# schematics_easyeda.net
KiCad netlist of a schematic drawn in EasyEDA
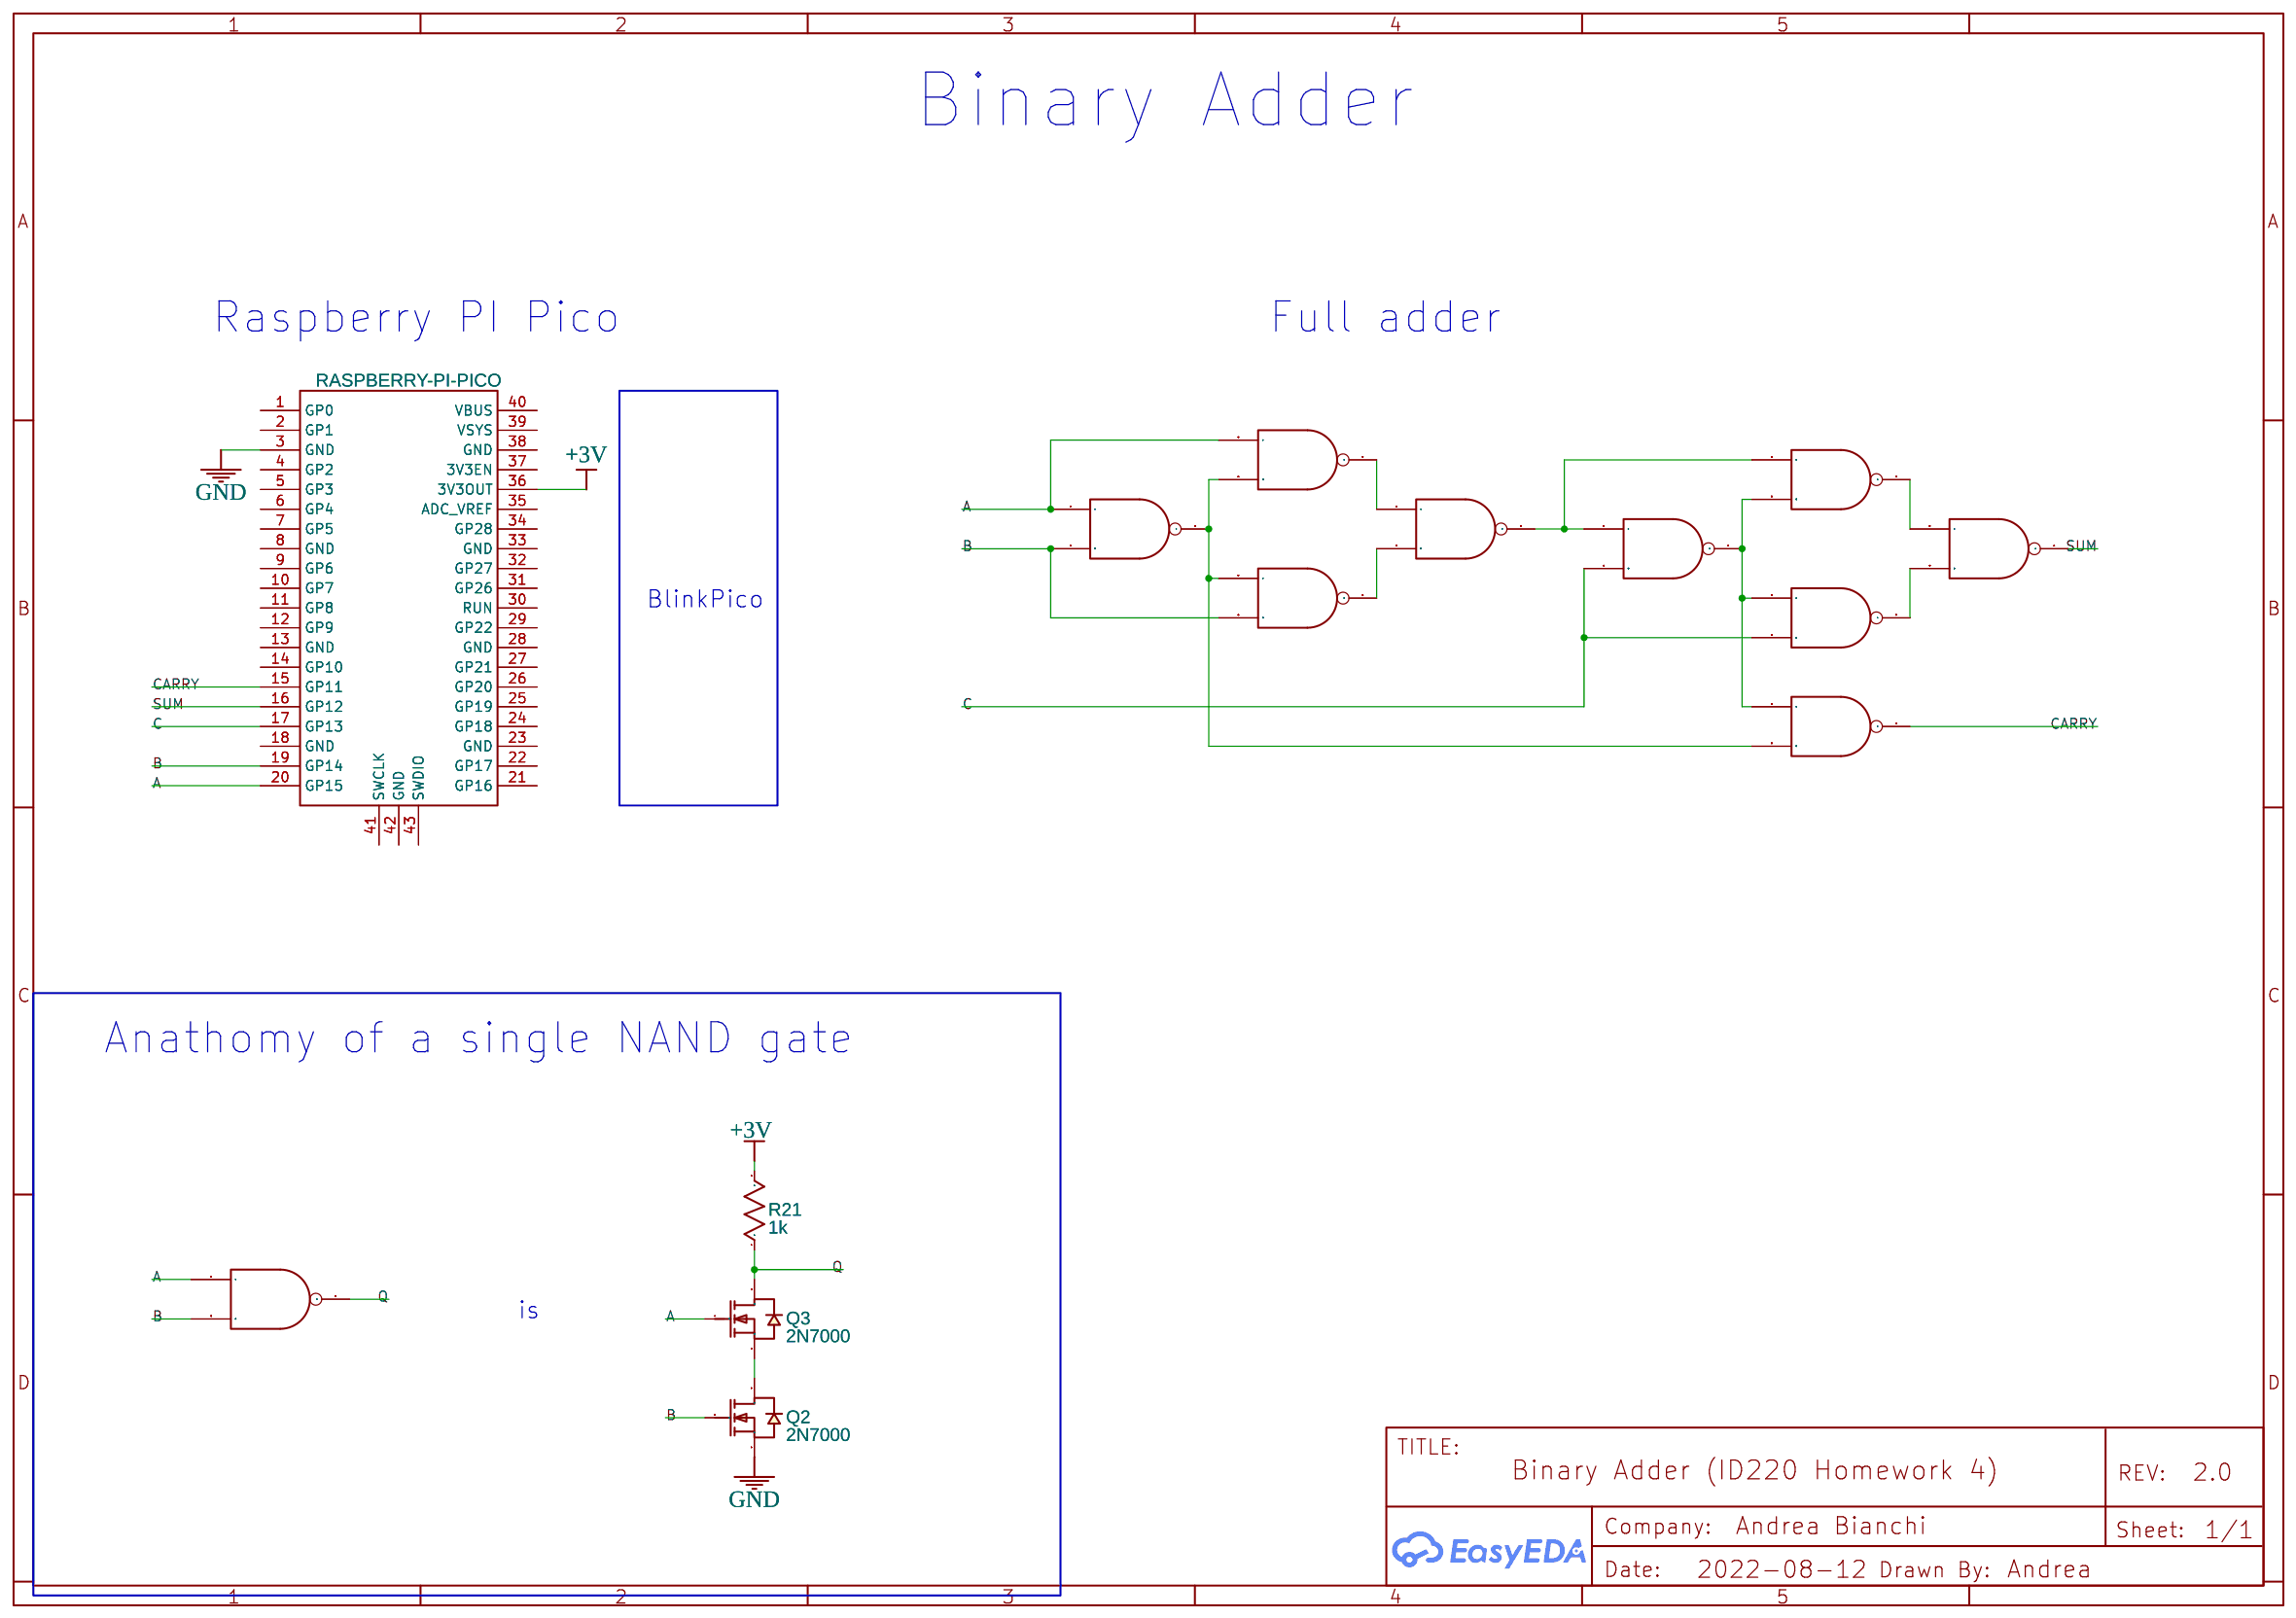
[diagram p0: schematic sheet]

(export (version "E")
  (design (tool "Eeschema 10.0.6"))
  (components
    (comp (ref "NAND1")
      (value "NO")
      (fields (field (name "BOM_Manufacturer Part") "?"))
      (libsource (lib "") (part "Unknown_565_-545"))
    )
    (comp (ref "NAND2")
      (value "NO")
      (fields (field (name "BOM_Manufacturer Part") "?"))
      (libsource (lib "") (part "Unknown_650_-580"))
    )
    (comp (ref "NAND3")
      (value "NO")
      (fields (field (name "BOM_Manufacturer Part") "?"))
      (libsource (lib "") (part "Unknown_650_-510"))
    )
    (comp (ref "NAND4")
      (value "NO")
      (fields (field (name "BOM_Manufacturer Part") "?"))
      (libsource (lib "") (part "Unknown_730_-545"))
    )
    (comp (ref "NAND5")
      (value "NO")
      (fields (field (name "BOM_Manufacturer Part") "?"))
      (libsource (lib "") (part "Unknown_1000_-535"))
    )
    (comp (ref "NAND6")
      (value "NO")
      (fields (field (name "BOM_Manufacturer Part") "?"))
      (libsource (lib "") (part "Unknown_920_-500"))
    )
    (comp (ref "NAND7")
      (value "NO")
      (fields (field (name "BOM_Manufacturer Part") "?"))
      (libsource (lib "") (part "Unknown_920_-570"))
    )
    (comp (ref "NAND8")
      (value "NO")
      (fields (field (name "BOM_Manufacturer Part") "?"))
      (libsource (lib "") (part "Unknown_835_-535"))
    )
    (comp (ref "NAND9")
      (value "NO")
      (fields (field (name "BOM_Manufacturer Part") "?"))
      (libsource (lib "") (part "Unknown_920_-445"))
    )
    (comp (ref "NAND10")
      (value "NO")
      (fields (field (name "BOM_Manufacturer Part") "?"))
      (libsource (lib "") (part "Unknown_130_-155"))
    )
    (comp (ref "Q2")
      (value "2N7000")
      (fields (field (name "BOM_Manufacturer Part") "2N7002,215") (field (name "BOM_Supplier Part") "C65189"))
      (libsource (lib "") (part "2N7002"))
    )
    (comp (ref "Q3")
      (value "2N7000")
      (fields (field (name "BOM_Manufacturer Part") "2N7002,215") (field (name "BOM_Supplier Part") "C65189"))
      (libsource (lib "") (part "2N7002"))
    )
    (comp (ref "R21") (value "1k") (libsource (lib "") (part "R_0603_US")))
    (comp (ref "U4") (value "RASPBERRY-PI-PICO") (libsource (lib "") (part "RASPBERRY-PI-PICO")))
  )
  (nets
    (net (code "1") (name "+3V") (class "Default")
      (node (ref "R21") (pin "2") (pinfunction "2_2") (pintype "unspecified"))
      (node (ref "U4") (pin "36") (pinfunction "3V3OUT_36") (pintype "unspecified"))
    )
    (net (code "2") (name "/A") (class "Default")
      (node (ref "NAND1") (pin "12") (pinfunction "A_12") (pintype "unspecified"))
      (node (ref "NAND10") (pin "12") (pinfunction "A_12") (pintype "unspecified"))
      (node (ref "NAND2") (pin "12") (pinfunction "A_12") (pintype "unspecified"))
      (node (ref "Q3") (pin "1") (pinfunction "G_1") (pintype "unspecified"))
      (node (ref "U4") (pin "20") (pinfunction "GP15_20") (pintype "unspecified"))
    )
    (net (code "3") (name "/B") (class "Default")
      (node (ref "NAND1") (pin "13") (pinfunction "B_13") (pintype "unspecified"))
      (node (ref "NAND10") (pin "13") (pinfunction "B_13") (pintype "unspecified"))
      (node (ref "NAND3") (pin "13") (pinfunction "B_13") (pintype "unspecified"))
      (node (ref "Q2") (pin "1") (pinfunction "G_1") (pintype "unspecified"))
      (node (ref "U4") (pin "19") (pinfunction "GP14_19") (pintype "unspecified"))
    )
    (net (code "4") (name "/C") (class "Default")
      (node (ref "NAND6") (pin "13") (pinfunction "B_13") (pintype "unspecified"))
      (node (ref "NAND8") (pin "13") (pinfunction "B_13") (pintype "unspecified"))
      (node (ref "U4") (pin "17") (pinfunction "GP13_17") (pintype "unspecified"))
    )
    (net (code "5") (name "/CARRY") (class "Default")
      (node (ref "NAND9") (pin "11") (pinfunction "Y_11") (pintype "output"))
      (node (ref "U4") (pin "15") (pinfunction "GP11_15") (pintype "unspecified"))
    )
    (net (code "6") (name "/Q") (class "Default")
      (node (ref "NAND10") (pin "11") (pinfunction "Y_11") (pintype "output"))
      (node (ref "Q3") (pin "3") (pinfunction "D_3") (pintype "unspecified"))
      (node (ref "R21") (pin "1") (pinfunction "1_1") (pintype "unspecified"))
    )
    (net (code "7") (name "/SUM") (class "Default")
      (node (ref "NAND5") (pin "11") (pinfunction "Y_11") (pintype "output"))
      (node (ref "U4") (pin "16") (pinfunction "GP12_16") (pintype "unspecified"))
    )
    (net (code "8") (name "GND") (class "Default")
      (node (ref "Q2") (pin "2") (pinfunction "S_2") (pintype "unspecified"))
      (node (ref "U4") (pin "3") (pinfunction "GND_3") (pintype "unspecified"))
    )
    (net (code "9") (name "Net-(NAND1-Y)") (class "Default")
      (node (ref "NAND1") (pin "11") (pinfunction "Y_11") (pintype "output"))
      (node (ref "NAND2") (pin "13") (pinfunction "B_13") (pintype "unspecified"))
      (node (ref "NAND3") (pin "12") (pinfunction "A_12") (pintype "unspecified"))
      (node (ref "NAND9") (pin "13") (pinfunction "B_13") (pintype "unspecified"))
    )
    (net (code "10") (name "Net-(NAND2-Y)") (class "Default")
      (node (ref "NAND2") (pin "11") (pinfunction "Y_11") (pintype "output"))
      (node (ref "NAND4") (pin "12") (pinfunction "A_12") (pintype "unspecified"))
    )
    (net (code "11") (name "Net-(NAND3-Y)") (class "Default")
      (node (ref "NAND3") (pin "11") (pinfunction "Y_11") (pintype "output"))
      (node (ref "NAND4") (pin "13") (pinfunction "B_13") (pintype "unspecified"))
    )
    (net (code "12") (name "Net-(NAND4-Y)") (class "Default")
      (node (ref "NAND4") (pin "11") (pinfunction "Y_11") (pintype "output"))
      (node (ref "NAND7") (pin "12") (pinfunction "A_12") (pintype "unspecified"))
      (node (ref "NAND8") (pin "12") (pinfunction "A_12") (pintype "unspecified"))
    )
    (net (code "13") (name "Net-(NAND5-A)") (class "Default")
      (node (ref "NAND5") (pin "12") (pinfunction "A_12") (pintype "unspecified"))
      (node (ref "NAND7") (pin "11") (pinfunction "Y_11") (pintype "output"))
    )
    (net (code "14") (name "Net-(NAND5-B)") (class "Default")
      (node (ref "NAND5") (pin "13") (pinfunction "B_13") (pintype "unspecified"))
      (node (ref "NAND6") (pin "11") (pinfunction "Y_11") (pintype "output"))
    )
    (net (code "15") (name "Net-(NAND6-A)") (class "Default")
      (node (ref "NAND6") (pin "12") (pinfunction "A_12") (pintype "unspecified"))
      (node (ref "NAND7") (pin "13") (pinfunction "B_13") (pintype "unspecified"))
      (node (ref "NAND8") (pin "11") (pinfunction "Y_11") (pintype "output"))
      (node (ref "NAND9") (pin "12") (pinfunction "A_12") (pintype "unspecified"))
    )
    (net (code "16") (name "Net-(Q2-D)") (class "Default")
      (node (ref "Q2") (pin "3") (pinfunction "D_3") (pintype "unspecified"))
      (node (ref "Q3") (pin "2") (pinfunction "S_2") (pintype "unspecified"))
    )
    (net (code "17") (name "unconnected-(U4-3V3EN-Pad37)") (class "Default")
      (node (ref "U4") (pin "37") (pinfunction "3V3EN_37") (pintype "unspecified"))
    )
    (net (code "18") (name "unconnected-(U4-ADC_VREF-Pad35)") (class "Default")
      (node (ref "U4") (pin "35") (pinfunction "ADC_VREF_35") (pintype "unspecified"))
    )
    (net (code "19") (name "unconnected-(U4-GND-Pad8)") (class "Default")
      (node (ref "U4") (pin "8") (pinfunction "GND_8") (pintype "unspecified"))
    )
    (net (code "20") (name "unconnected-(U4-GND-Pad13)") (class "Default")
      (node (ref "U4") (pin "13") (pinfunction "GND_13") (pintype "unspecified"))
    )
    (net (code "21") (name "unconnected-(U4-GND-Pad18)") (class "Default")
      (node (ref "U4") (pin "18") (pinfunction "GND_18") (pintype "unspecified"))
    )
    (net (code "22") (name "unconnected-(U4-GND-Pad23)") (class "Default")
      (node (ref "U4") (pin "23") (pinfunction "GND_23") (pintype "unspecified"))
    )
    (net (code "23") (name "unconnected-(U4-GND-Pad28)") (class "Default")
      (node (ref "U4") (pin "28") (pinfunction "GND_28") (pintype "unspecified"))
    )
    (net (code "24") (name "unconnected-(U4-GND-Pad33)") (class "Default")
      (node (ref "U4") (pin "33") (pinfunction "GND_33") (pintype "unspecified"))
    )
    (net (code "25") (name "unconnected-(U4-GND-Pad38)") (class "Default")
      (node (ref "U4") (pin "38") (pinfunction "GND_38") (pintype "unspecified"))
    )
    (net (code "26") (name "unconnected-(U4-GND-Pad42)") (class "Default")
      (node (ref "U4") (pin "42") (pinfunction "GND_42") (pintype "unspecified"))
    )
    (net (code "27") (name "unconnected-(U4-GP0-Pad1)") (class "Default")
      (node (ref "U4") (pin "1") (pinfunction "GP0_1") (pintype "unspecified"))
    )
    (net (code "28") (name "unconnected-(U4-GP1-Pad2)") (class "Default")
      (node (ref "U4") (pin "2") (pinfunction "GP1_2") (pintype "unspecified"))
    )
    (net (code "29") (name "unconnected-(U4-GP2-Pad4)") (class "Default")
      (node (ref "U4") (pin "4") (pinfunction "GP2_4") (pintype "unspecified"))
    )
    (net (code "30") (name "unconnected-(U4-GP3-Pad5)") (class "Default")
      (node (ref "U4") (pin "5") (pinfunction "GP3_5") (pintype "unspecified"))
    )
    (net (code "31") (name "unconnected-(U4-GP4-Pad6)") (class "Default")
      (node (ref "U4") (pin "6") (pinfunction "GP4_6") (pintype "unspecified"))
    )
    (net (code "32") (name "unconnected-(U4-GP5-Pad7)") (class "Default")
      (node (ref "U4") (pin "7") (pinfunction "GP5_7") (pintype "unspecified"))
    )
    (net (code "33") (name "unconnected-(U4-GP6-Pad9)") (class "Default")
      (node (ref "U4") (pin "9") (pinfunction "GP6_9") (pintype "unspecified"))
    )
    (net (code "34") (name "unconnected-(U4-GP7-Pad10)") (class "Default")
      (node (ref "U4") (pin "10") (pinfunction "GP7_10") (pintype "unspecified"))
    )
    (net (code "35") (name "unconnected-(U4-GP8-Pad11)") (class "Default")
      (node (ref "U4") (pin "11") (pinfunction "GP8_11") (pintype "unspecified"))
    )
    (net (code "36") (name "unconnected-(U4-GP9-Pad12)") (class "Default")
      (node (ref "U4") (pin "12") (pinfunction "GP9_12") (pintype "unspecified"))
    )
    (net (code "37") (name "unconnected-(U4-GP10-Pad14)") (class "Default")
      (node (ref "U4") (pin "14") (pinfunction "GP10_14") (pintype "unspecified"))
    )
    (net (code "38") (name "unconnected-(U4-GP16-Pad21)") (class "Default")
      (node (ref "U4") (pin "21") (pinfunction "GP16_21") (pintype "unspecified"))
    )
    (net (code "39") (name "unconnected-(U4-GP17-Pad22)") (class "Default")
      (node (ref "U4") (pin "22") (pinfunction "GP17_22") (pintype "unspecified"))
    )
    (net (code "40") (name "unconnected-(U4-GP18-Pad24)") (class "Default")
      (node (ref "U4") (pin "24") (pinfunction "GP18_24") (pintype "unspecified"))
    )
    (net (code "41") (name "unconnected-(U4-GP19-Pad25)") (class "Default")
      (node (ref "U4") (pin "25") (pinfunction "GP19_25") (pintype "unspecified"))
    )
    (net (code "42") (name "unconnected-(U4-GP20-Pad26)") (class "Default")
      (node (ref "U4") (pin "26") (pinfunction "GP20_26") (pintype "unspecified"))
    )
    (net (code "43") (name "unconnected-(U4-GP21-Pad27)") (class "Default")
      (node (ref "U4") (pin "27") (pinfunction "GP21_27") (pintype "unspecified"))
    )
    (net (code "44") (name "unconnected-(U4-GP22-Pad29)") (class "Default")
      (node (ref "U4") (pin "29") (pinfunction "GP22_29") (pintype "unspecified"))
    )
    (net (code "45") (name "unconnected-(U4-GP26-Pad31)") (class "Default")
      (node (ref "U4") (pin "31") (pinfunction "GP26_31") (pintype "unspecified"))
    )
    (net (code "46") (name "unconnected-(U4-GP27-Pad32)") (class "Default")
      (node (ref "U4") (pin "32") (pinfunction "GP27_32") (pintype "unspecified"))
    )
    (net (code "47") (name "unconnected-(U4-GP28-Pad34)") (class "Default")
      (node (ref "U4") (pin "34") (pinfunction "GP28_34") (pintype "unspecified"))
    )
    (net (code "48") (name "unconnected-(U4-RUN-Pad30)") (class "Default")
      (node (ref "U4") (pin "30") (pinfunction "RUN_30") (pintype "unspecified"))
    )
    (net (code "49") (name "unconnected-(U4-SWCLK-Pad41)") (class "Default")
      (node (ref "U4") (pin "41") (pinfunction "SWCLK_41") (pintype "unspecified"))
    )
    (net (code "50") (name "unconnected-(U4-SWDIO-Pad43)") (class "Default")
      (node (ref "U4") (pin "43") (pinfunction "SWDIO_43") (pintype "unspecified"))
    )
    (net (code "51") (name "unconnected-(U4-VBUS-Pad40)") (class "Default")
      (node (ref "U4") (pin "40") (pinfunction "VBUS_40") (pintype "unspecified"))
    )
    (net (code "52") (name "unconnected-(U4-VSYS-Pad39)") (class "Default")
      (node (ref "U4") (pin "39") (pinfunction "VSYS_39") (pintype "unspecified"))
    )
  )
)
